# IoT_Greenhouse_V1_0_A_-_Esp32.net
KiCad netlist of a schematic drawn in Altium Designer
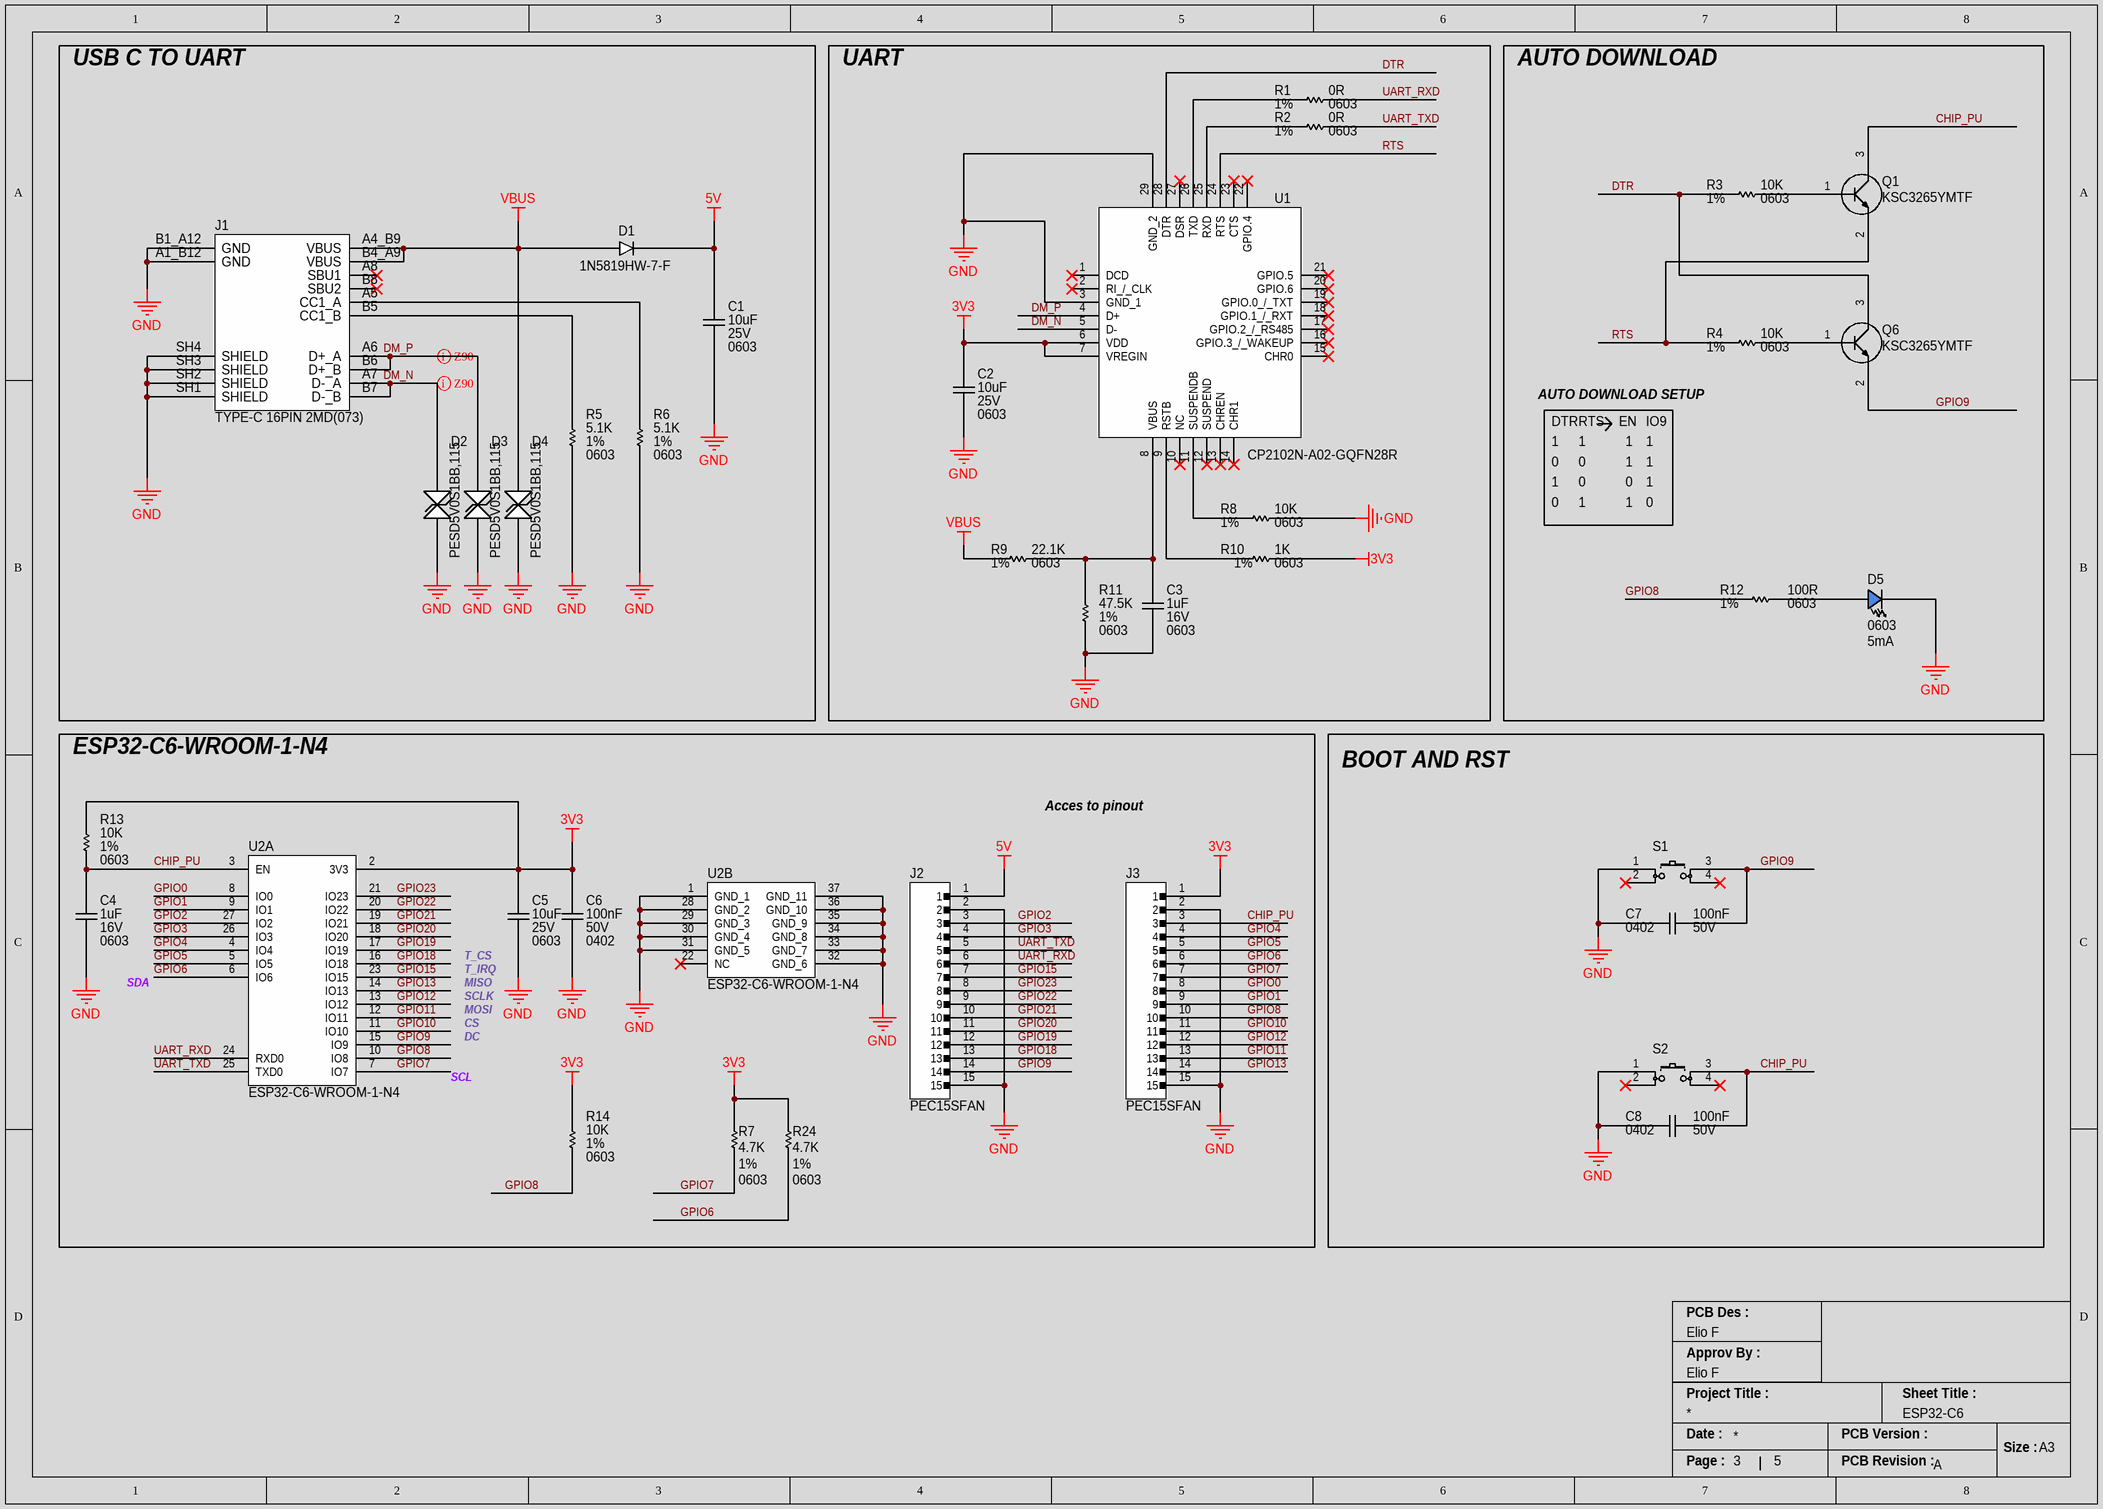
[diagram p0: IoT_Greenhouse V1.0 A - Esp32.SchDoc]

(export (version "E")
  (design (tool "Eeschema 10.0.6"))
  (components
    (comp (ref "C1")
      (value "GRM188R61E106MA73D")
      (footprint "CAP_0603_CAPC1608X08N")
      (description "Multilayer Ceramic Capacitor, 10 uF, 25 V, ± 20%, X5R, 0603 [1608 Metric]")
      (fields
        (field (name "MANUFACTURER") "Murata")
        (field (name "TOLERANCE") "20%")
        (field (name "CASE/PACKAGE") "0603")
        (field (name "CAPACITANCE") "10uF")
        (field (name "VOLTAGE RATING") "25V")
      )
      (libsource (lib "Electronic Devices_LIB") (part "CAP_10UF_25V_X5R_0603"))
    )
    (comp (ref "C2")
      (value "GRM188R61E106MA73D")
      (footprint "CAP_0603_CAPC1608X08N")
      (description "Multilayer Ceramic Capacitor, 10 uF, 25 V, ± 20%, X5R, 0603 [1608 Metric]")
      (fields
        (field (name "MANUFACTURER") "Murata")
        (field (name "TOLERANCE") "20%")
        (field (name "CASE/PACKAGE") "0603")
        (field (name "CAPACITANCE") "10uF")
        (field (name "VOLTAGE RATING") "25V")
      )
      (libsource (lib "Electronic Devices_LIB") (part "CAP_10UF_25V_X5R_0603"))
    )
    (comp (ref "C3")
      (value "CL10A105KO8NNNC")
      (footprint "CAP_0603_CAPC1608X08N")
      (description "CAP CER 1UF 16V X5R 0603")
      (fields
        (field (name "MANUFACTURER") "Samsung")
        (field (name "TOLERANCE") "10%")
        (field (name "VOLTAGE RATING") "16V")
        (field (name "CAPACITANCE") "1uF")
        (field (name "CASE/PACKAGE") "0603")
      )
      (libsource (lib "Electronic Devices_LIB") (part "CAP_1UF_16V_X5R_0603"))
    )
    (comp (ref "C4")
      (value "CL10A105KO8NNNC")
      (footprint "CAP_0603_CAPC1608X08N")
      (description "CAP CER 1UF 16V X5R 0603")
      (fields
        (field (name "MANUFACTURER") "Samsung")
        (field (name "TOLERANCE") "10%")
        (field (name "VOLTAGE RATING") "16V")
        (field (name "CAPACITANCE") "1uF")
        (field (name "CASE/PACKAGE") "0603")
      )
      (libsource (lib "Electronic Devices_LIB") (part "CAP_1UF_16V_X5R_0603"))
    )
    (comp (ref "C5")
      (value "GRM188R61E106MA73D")
      (footprint "CAP_0603_CAPC1608X08N")
      (description "Multilayer Ceramic Capacitor, 10 uF, 25 V, ± 20%, X5R, 0603 [1608 Metric]")
      (fields
        (field (name "MANUFACTURER") "Murata")
        (field (name "TOLERANCE") "20%")
        (field (name "CASE/PACKAGE") "0603")
        (field (name "CAPACITANCE") "10uF")
        (field (name "VOLTAGE RATING") "25V")
      )
      (libsource (lib "Electronic Devices_LIB") (part "CAP_10UF_25V_X5R_0603"))
    )
    (comp (ref "C6")
      (value "GRM155R71H104KE14D")
      (footprint "CAP_0402_CAPC1005X05N")
      (description "Multilayer Ceramic Capacitor, 0.1 uF, 16 V, ± 10%, X7R, 0402 [1005 Metric]")
      (fields
        (field (name "MANUFACTURER") "Murata")
        (field (name "TOLERANCE") "10%")
        (field (name "VOLTAGE RATING") "50V")
        (field (name "CAPACITANCE") "100nF")
        (field (name "CASE/PACKAGE") "0402")
      )
      (libsource (lib "Electronic Devices_LIB") (part "CAP_100NF_50V_X7R_0402"))
    )
    (comp (ref "C7")
      (value "GRM155R71H104KE14D")
      (footprint "CAP_0402_CAPC1005X05N")
      (description "Multilayer Ceramic Capacitor, 0.1 uF, 16 V, ± 10%, X7R, 0402 [1005 Metric]")
      (fields
        (field (name "MANUFACTURER") "Murata")
        (field (name "TOLERANCE") "10%")
        (field (name "VOLTAGE RATING") "50V")
        (field (name "CAPACITANCE") "100nF")
        (field (name "CASE/PACKAGE") "0402")
      )
      (libsource (lib "Electronic Devices_LIB") (part "CAP_100NF_50V_X7R_0402"))
    )
    (comp (ref "C8")
      (value "GRM155R71H104KE14D")
      (footprint "CAP_0402_CAPC1005X05N")
      (description "Multilayer Ceramic Capacitor, 0.1 uF, 16 V, ± 10%, X7R, 0402 [1005 Metric]")
      (fields
        (field (name "MANUFACTURER") "Murata")
        (field (name "TOLERANCE") "10%")
        (field (name "VOLTAGE RATING") "50V")
        (field (name "CAPACITANCE") "100nF")
        (field (name "CASE/PACKAGE") "0402")
      )
      (libsource (lib "Electronic Devices_LIB") (part "CAP_100NF_50V_X7R_0402"))
    )
    (comp (ref "D1")
      (value "1N5819HW-7-F")
      (footprint "DIO_SOD3716X145N")
      (description "Rectifier Diode, Schottky, 1 Phase, 1 Element, 1A, 40V V(RRM), Silicon")
      (fields (field (name "MANUFACTURER") "Diodes"))
      (libsource (lib "Electronic Devices_LIB") (part "DIO_RECT_40V_1A_1N5819HW-7-F"))
    )
    (comp (ref "D2")
      (value "PESD5V0S1BB,115")
      (footprint "DIO_TVS_SODFL1608X65N")
      (description "ESD Suppressor Diode TVS Bi-Dir 5V Automotive 2-Pin SOD-523 T/R / TVS DIODE 5VWM 14VC SOD523")
      (fields (field (name "MANUFACTURER") "Nexperia"))
      (libsource (lib "Electronic Devices_LIB") (part "DIO_TVS_BID_5V_PESD5V0S1BB,115"))
    )
    (comp (ref "D3")
      (value "PESD5V0S1BB,115")
      (footprint "DIO_TVS_SODFL1608X65N")
      (description "ESD Suppressor Diode TVS Bi-Dir 5V Automotive 2-Pin SOD-523 T/R / TVS DIODE 5VWM 14VC SOD523")
      (fields (field (name "MANUFACTURER") "Nexperia"))
      (libsource (lib "Electronic Devices_LIB") (part "DIO_TVS_BID_5V_PESD5V0S1BB,115"))
    )
    (comp (ref "D4")
      (value "PESD5V0S1BB,115")
      (footprint "DIO_TVS_SODFL1608X65N")
      (description "ESD Suppressor Diode TVS Bi-Dir 5V Automotive 2-Pin SOD-523 T/R / TVS DIODE 5VWM 14VC SOD523")
      (fields (field (name "MANUFACTURER") "Nexperia"))
      (libsource (lib "Electronic Devices_LIB") (part "DIO_TVS_BID_5V_PESD5V0S1BB,115"))
    )
    (comp (ref "D5")
      (value "LTST-C193TBKT-5A")
      (footprint "LED_0603-BLUE-0.75mm")
      (description "LED Uni-Color Blue 468nm 2-Pin Chip LED T/R")
      (fields
        (field (name "MANUFACTURER") "Vishay Lite-On")
        (field (name "CASE CODE (IMPERIAL)") "0603")
        (field (name "TEST CURRENT") "5mA")
      )
      (libsource (lib "Electronic Devices_LIB") (part "LED_DIO_BLUE_5mA_0603"))
    )
    (comp (ref "J1")
      (value "TYPE-C 16PIN 2MD(073)")
      (footprint "CONN_USB_C_16P")
      (description "5A 1 Surface Mount 16P Female -25℃~+85℃ Type-C SMD USB Connectors ROHS")
      (fields (field (name "MANUFACTURER") "SHOU HAN"))
      (libsource (lib "Electronic Devices_LIB") (part "CONN_USB_TYPEC_2.0_16P_TYPE-C 16PIN 2MD(073)"))
    )
    (comp (ref "J2")
      (value "PEC15SFAN")
      (footprint "HEADER_MALE_15P")
      (description "CONN HEADER .100 SINGL STR 15POS")
      (fields (field (name "MANUFACTURER") "Sullins"))
      (libsource (lib "Electronic Devices_LIB") (part "CONN_HEADER_MALE_15P_2.54mm"))
    )
    (comp (ref "J3")
      (value "PEC15SFAN")
      (footprint "HEADER_MALE_15P")
      (description "CONN HEADER .100 SINGL STR 15POS")
      (fields (field (name "MANUFACTURER") "Sullins"))
      (libsource (lib "Electronic Devices_LIB") (part "CONN_HEADER_MALE_15P_2.54mm"))
    )
    (comp (ref "Q1")
      (value "KSC3265YMTF")
      (footprint "TRANS_BJT_SOT96P237X111-3N")
      (description "KSC3265 Series 25 V CE Breakdown .8 A NPN Epitaxial Silicon Transistor - SOT-23")
      (fields (field (name "MANUFACTURER") "ON Semiconductor / Fairchild"))
      (libsource (lib "Electronic Devices_LIB") (part "TRANS_BJT_NPN_800mA_25V_KSC3265YMTF"))
    )
    (comp (ref "Q6")
      (value "KSC3265YMTF")
      (footprint "TRANS_BJT_SOT96P237X111-3N")
      (description "KSC3265 Series 25 V CE Breakdown .8 A NPN Epitaxial Silicon Transistor - SOT-23")
      (fields (field (name "MANUFACTURER") "ON Semiconductor / Fairchild"))
      (libsource (lib "Electronic Devices_LIB") (part "TRANS_BJT_NPN_800mA_25V_KSC3265YMTF"))
    )
    (comp (ref "R1")
      (value "RC0603FR-070RL")
      (footprint "RES_0603_RESC1608X04N")
      (description "RC Series 0603 0.1 W 0 Ohm Jumper Surface Mount Thick Film Chip Resistor")
      (fields
        (field (name "MANUFACTURER") "Yageo")
        (field (name "TOLERANCE") "1%")
        (field (name "RESISTANCE") "0R")
        (field (name "CASE CODE (IMPERIAL)") "0603")
      )
      (libsource (lib "Electronic Devices_LIB") (part "RES_0R_1%_100mW_0603"))
    )
    (comp (ref "R2")
      (value "RC0603FR-070RL")
      (footprint "RES_0603_RESC1608X04N")
      (description "RC Series 0603 0.1 W 0 Ohm Jumper Surface Mount Thick Film Chip Resistor")
      (fields
        (field (name "MANUFACTURER") "Yageo")
        (field (name "TOLERANCE") "1%")
        (field (name "RESISTANCE") "0R")
        (field (name "CASE CODE (IMPERIAL)") "0603")
      )
      (libsource (lib "Electronic Devices_LIB") (part "RES_0R_1%_100mW_0603"))
    )
    (comp (ref "R3")
      (value "AC0603FR-1010KL")
      (footprint "RES_0603_RESC1608X04N")
      (description "Chip Resistor Automotive Grade Thick Film 0603 10kOhm 1% Paper T/R")
      (fields
        (field (name "MANUFACTURER") "Yageo")
        (field (name "RESISTANCE") "10K")
        (field (name "TOLERANCE") "1%")
        (field (name "CASE/PACKAGE") "0603")
      )
      (libsource (lib "Electronic Devices_LIB") (part "RES_10K_1%_100mW_0603"))
    )
    (comp (ref "R4")
      (value "AC0603FR-1010KL")
      (footprint "RES_0603_RESC1608X04N")
      (description "Chip Resistor Automotive Grade Thick Film 0603 10kOhm 1% Paper T/R")
      (fields
        (field (name "MANUFACTURER") "Yageo")
        (field (name "RESISTANCE") "10K")
        (field (name "TOLERANCE") "1%")
        (field (name "CASE/PACKAGE") "0603")
      )
      (libsource (lib "Electronic Devices_LIB") (part "RES_10K_1%_100mW_0603"))
    )
    (comp (ref "R5")
      (value "RC0603FR-075K1L")
      (footprint "RES_0603_RESC1608X04N")
      (description "SMD Chip Resistor, 5.1 kOhm, ± 1%, 100 mW, 0603 [1608 Metric], Thick Film, General Purpose")
      (fields
        (field (name "MANUFACTURER") "Yageo")
        (field (name "TOLERANCE") "1%")
        (field (name "RESISTANCE") "5.1K")
        (field (name "CASE/PACKAGE") "0603")
      )
      (libsource (lib "Electronic Devices_LIB") (part "RES_5.1K_1%_100mW_0603"))
    )
    (comp (ref "R6")
      (value "RC0603FR-075K1L")
      (footprint "RES_0603_RESC1608X04N")
      (description "SMD Chip Resistor, 5.1 kOhm, ± 1%, 100 mW, 0603 [1608 Metric], Thick Film, General Purpose")
      (fields
        (field (name "MANUFACTURER") "Yageo")
        (field (name "TOLERANCE") "1%")
        (field (name "RESISTANCE") "5.1K")
        (field (name "CASE/PACKAGE") "0603")
      )
      (libsource (lib "Electronic Devices_LIB") (part "RES_5.1K_1%_100mW_0603"))
    )
    (comp (ref "R7")
      (value "RC0603FR-074K7L")
      (footprint "RES_0603_RESC1608X04N")
      (description "Res Thick Film 0603 4.7K Ohm 1% 1/10W ±100ppm/°C Molded SMD Paper T/R")
      (fields
        (field (name "MANUFACTURER") "Yageo")
        (field (name "RESISTANCE") "4.7K")
        (field (name "TOLERANCE") "1%")
        (field (name "CASE/PACKAGE") "0603")
      )
      (libsource (lib "Electronic Devices_LIB") (part "RES_4.7K_1%_100mW_0603"))
    )
    (comp (ref "R8")
      (value "AC0603FR-1010KL")
      (footprint "RES_0603_RESC1608X04N")
      (description "Chip Resistor Automotive Grade Thick Film 0603 10kOhm 1% Paper T/R")
      (fields
        (field (name "MANUFACTURER") "Yageo")
        (field (name "RESISTANCE") "10K")
        (field (name "TOLERANCE") "1%")
        (field (name "CASE/PACKAGE") "0603")
      )
      (libsource (lib "Electronic Devices_LIB") (part "RES_10K_1%_100mW_0603"))
    )
    (comp (ref "R9")
      (value "RC0603FR-0722K1L")
      (footprint "RES_0603_RESC1608X04N")
      (description "SMD Chip Resistor, 22.1 kOhm, ± 1%, 100 mW, 0603 [1608 Metric], Thick Film, General Purpose")
      (fields
        (field (name "MANUFACTURER") "Yageo")
        (field (name "RESISTANCE") "22.1K")
        (field (name "TOLERANCE") "1%")
        (field (name "CASE/PACKAGE") "0603")
      )
      (libsource (lib "Electronic Devices_LIB") (part "RES_22.1K_1%_100mW_0603"))
    )
    (comp (ref "R10")
      (value "AC0603FR-101KL")
      (footprint "RES_0603_RESC1608X04N")
      (description "Chip Resistor Automotive Grade Thick Film 0603 1kOhm 1% Paper T/R")
      (fields
        (field (name "MANUFACTURER") "Yageo")
        (field (name "RESISTANCE") "1K")
        (field (name "TOLERANCE") "1%")
        (field (name "CASE/PACKAGE") "0603")
      )
      (libsource (lib "Electronic Devices_LIB") (part "RES_1K_1%_100mW_0603"))
    )
    (comp (ref "R11")
      (value "AC0603FR-0747K5L")
      (footprint "RES_0603_RESC1608X04N")
      (description "SMD Chip Resistor, 47.5 kOhm, ± 1%, 100 mW, 0603 [1608 Metric], Thick Film, General Purpose")
      (fields
        (field (name "MANUFACTURER") "Yageo")
        (field (name "TOLERANCE") "1%")
        (field (name "RESISTANCE") "47.5K")
        (field (name "CASE/PACKAGE") "0603")
      )
      (libsource (lib "Electronic Devices_LIB") (part "RES_47.5K_1%_100mW_0603"))
    )
    (comp (ref "R12")
      (value "ERJ3EKF1000V")
      (footprint "CAP_0603_CAPC1608X08N")
      (description "Res Thick Film 0603 100 Ohm 1% 1/10W ±100ppm/°C Molded SMD Punched Carrier T/R")
      (fields
        (field (name "MANUFACTURER") "Panasonic")
        (field (name "CASE CODE (IMPERIAL)") "0603")
        (field (name "TOLERANCE") "1%")
        (field (name "RESISTANCE") "100R")
      )
      (libsource (lib "Electronic Devices_LIB") (part "RES_100R_1%_100MW_0603"))
    )
    (comp (ref "R13")
      (value "AC0603FR-1010KL")
      (footprint "RES_0603_RESC1608X04N")
      (description "Chip Resistor Automotive Grade Thick Film 0603 10kOhm 1% Paper T/R")
      (fields
        (field (name "MANUFACTURER") "Yageo")
        (field (name "RESISTANCE") "10K")
        (field (name "TOLERANCE") "1%")
        (field (name "CASE/PACKAGE") "0603")
      )
      (libsource (lib "Electronic Devices_LIB") (part "RES_10K_1%_100mW_0603"))
    )
    (comp (ref "R14")
      (value "AC0603FR-1010KL")
      (footprint "RES_0603_RESC1608X04N")
      (description "Chip Resistor Automotive Grade Thick Film 0603 10kOhm 1% Paper T/R")
      (fields
        (field (name "MANUFACTURER") "Yageo")
        (field (name "RESISTANCE") "10K")
        (field (name "TOLERANCE") "1%")
        (field (name "CASE/PACKAGE") "0603")
      )
      (libsource (lib "Electronic Devices_LIB") (part "RES_10K_1%_100mW_0603"))
    )
    (comp (ref "R24")
      (value "RC0603FR-074K7L")
      (footprint "RES_0603_RESC1608X04N")
      (description "Res Thick Film 0603 4.7K Ohm 1% 1/10W ±100ppm/°C Molded SMD Paper T/R")
      (fields
        (field (name "MANUFACTURER") "Yageo")
        (field (name "RESISTANCE") "4.7K")
        (field (name "TOLERANCE") "1%")
        (field (name "CASE/PACKAGE") "0603")
      )
      (libsource (lib "Electronic Devices_LIB") (part "RES_4.7K_1%_100mW_0603"))
    )
    (comp (ref "S1")
      (value "PTS526SK15SMTR2LFS")
      (footprint "SWT_NO_PTS526SK15SMTR2LFS")
      (description "Switch Tactile N.O. SPST Round Button Gull Wing 0.05A 12VDC 200000Cycles 2.55N SMD T/R")
      (fields (field (name "MANUFACTURER") "ITT C&K"))
      (libsource (lib "Electronic Devices_LIB") (part "SWITCH_NO_SPST_0.05A"))
    )
    (comp (ref "S2")
      (value "PTS526SK15SMTR2LFS")
      (footprint "SWT_NO_PTS526SK15SMTR2LFS")
      (description "Switch Tactile N.O. SPST Round Button Gull Wing 0.05A 12VDC 200000Cycles 2.55N SMD T/R")
      (fields (field (name "MANUFACTURER") "ITT C&K"))
      (libsource (lib "Electronic Devices_LIB") (part "SWITCH_NO_SPST_0.05A"))
    )
    (comp (ref "U1")
      (value "CP2102N-A02-GQFN28R")
      (footprint "IC_BRIDGE_UART_QFN50P500X500X80-29N-D")
      (description "Full Speed USB to UART Bridge USB 2.0 3.3V T/R Automotive 28-Pin QFN EP")
      (fields (field (name "MANUFACTURER") "Silicon Labs"))
      (libsource (lib "Electronic Devices_LIB") (part "IC_BRIDGE_UART_CP2102N-A02-GQFN28R"))
    )
    (comp (ref "U2")
      (value "ESP32-C6-WROOM-1-N4")
      (footprint "IC_MODULE_ESP32C6WROOM1N4")
      (description "ESP32-C6-WROOM-1-N4 Engineering Module - 4 MB Quad SPI Flash")
      (fields (field (name "MANUFACTURER") "Espressif Systems"))
      (libsource (lib "Electronic Devices_LIB") (part "IC_MODULE_ESP32-C6-WROOM-1-N4"))
    )
  )
  (nets
    (net (code "1") (name "/CHIP_PU") (class "Default")
      (node (ref "C4") (pin "2") (pinfunction "2_2") (pintype "passive"))
      (node (ref "C8") (pin "1") (pinfunction "1_1") (pintype "passive"))
      (node (ref "J3") (pin "3") (pinfunction "3_3") (pintype "passive"))
      (node (ref "Q1") (pin "3") (pinfunction "C_3") (pintype "passive"))
      (node (ref "R13") (pin "2") (pinfunction "2_2") (pintype "passive"))
      (node (ref "S2") (pin "3") (pinfunction "NO1_3") (pintype "passive"))
      (node (ref "U2") (pin "3") (pinfunction "EN_3") (pintype "passive"))
    )
    (net (code "2") (name "/DM_N") (class "Default")
      (node (ref "D2") (pin "2") (pinfunction "K2_2") (pintype "passive"))
      (node (ref "J1") (pin "A7") (pinfunction "D-_A_A7") (pintype "passive"))
      (node (ref "J1") (pin "B7") (pinfunction "D-_B_B7") (pintype "passive"))
      (node (ref "U1") (pin "5") (pinfunction "D-_5") (pintype "passive"))
    )
    (net (code "3") (name "/DM_P") (class "Default")
      (node (ref "D3") (pin "2") (pinfunction "K2_2") (pintype "passive"))
      (node (ref "J1") (pin "A6") (pinfunction "D+_A_A6") (pintype "passive"))
      (node (ref "J1") (pin "B6") (pinfunction "D+_B_B6") (pintype "passive"))
      (node (ref "U1") (pin "4") (pinfunction "D+_4") (pintype "passive"))
    )
    (net (code "4") (name "/DTR") (class "Default")
      (node (ref "Q6") (pin "3") (pinfunction "C_3") (pintype "passive"))
      (node (ref "R3") (pin "2") (pinfunction "2_2") (pintype "passive"))
      (node (ref "U1") (pin "28") (pinfunction "DTR_28") (pintype "passive"))
    )
    (net (code "5") (name "/GPIO0") (class "Default")
      (node (ref "J3") (pin "8") (pinfunction "8_8") (pintype "passive"))
      (node (ref "U2") (pin "8") (pinfunction "IO0_8") (pintype "passive"))
    )
    (net (code "6") (name "/GPIO1") (class "Default")
      (node (ref "J3") (pin "9") (pinfunction "9_9") (pintype "passive"))
      (node (ref "U2") (pin "9") (pinfunction "IO1_9") (pintype "passive"))
    )
    (net (code "7") (name "/GPIO2") (class "Default")
      (node (ref "J2") (pin "3") (pinfunction "3_3") (pintype "passive"))
      (node (ref "U2") (pin "27") (pinfunction "IO2_27") (pintype "passive"))
    )
    (net (code "8") (name "/GPIO3") (class "Default")
      (node (ref "J2") (pin "4") (pinfunction "4_4") (pintype "passive"))
      (node (ref "U2") (pin "26") (pinfunction "IO3_26") (pintype "passive"))
    )
    (net (code "9") (name "/GPIO4") (class "Default")
      (node (ref "J3") (pin "4") (pinfunction "4_4") (pintype "passive"))
      (node (ref "U2") (pin "4") (pinfunction "IO4_4") (pintype "passive"))
    )
    (net (code "10") (name "/GPIO5") (class "Default")
      (node (ref "J3") (pin "5") (pinfunction "5_5") (pintype "passive"))
      (node (ref "U2") (pin "5") (pinfunction "IO5_5") (pintype "passive"))
    )
    (net (code "11") (name "/GPIO6") (class "Default")
      (node (ref "J3") (pin "6") (pinfunction "6_6") (pintype "passive"))
      (node (ref "R24") (pin "1") (pinfunction "1_1") (pintype "passive"))
      (node (ref "U2") (pin "6") (pinfunction "IO6_6") (pintype "passive"))
    )
    (net (code "12") (name "/GPIO7") (class "Default")
      (node (ref "J3") (pin "7") (pinfunction "7_7") (pintype "passive"))
      (node (ref "R7") (pin "1") (pinfunction "1_1") (pintype "passive"))
      (node (ref "U2") (pin "7") (pinfunction "IO7_7") (pintype "passive"))
    )
    (net (code "13") (name "/GPIO8") (class "Default")
      (node (ref "J3") (pin "10") (pinfunction "10_10") (pintype "passive"))
      (node (ref "R12") (pin "1") (pinfunction "1_1") (pintype "passive"))
      (node (ref "R14") (pin "2") (pinfunction "2_2") (pintype "passive"))
      (node (ref "U2") (pin "10") (pinfunction "IO8_10") (pintype "passive"))
    )
    (net (code "14") (name "/GPIO9") (class "Default")
      (node (ref "C7") (pin "1") (pinfunction "1_1") (pintype "passive"))
      (node (ref "J2") (pin "14") (pinfunction "14_14") (pintype "passive"))
      (node (ref "Q6") (pin "2") (pinfunction "E_2") (pintype "passive"))
      (node (ref "S1") (pin "3") (pinfunction "NO1_3") (pintype "passive"))
      (node (ref "U2") (pin "15") (pinfunction "IO9_15") (pintype "passive"))
    )
    (net (code "15") (name "/GPIO10") (class "Default")
      (node (ref "J3") (pin "11") (pinfunction "11_11") (pintype "passive"))
      (node (ref "U2") (pin "11") (pinfunction "IO10_11") (pintype "passive"))
    )
    (net (code "16") (name "/GPIO11") (class "Default")
      (node (ref "J3") (pin "13") (pinfunction "13_13") (pintype "passive"))
      (node (ref "U2") (pin "12") (pinfunction "IO11_12") (pintype "passive"))
    )
    (net (code "17") (name "/GPIO12") (class "Default")
      (node (ref "J3") (pin "12") (pinfunction "12_12") (pintype "passive"))
      (node (ref "U2") (pin "13") (pinfunction "IO12_13") (pintype "passive"))
    )
    (net (code "18") (name "/GPIO13") (class "Default")
      (node (ref "J3") (pin "14") (pinfunction "14_14") (pintype "passive"))
      (node (ref "U2") (pin "14") (pinfunction "IO13_14") (pintype "passive"))
    )
    (net (code "19") (name "/GPIO15") (class "Default")
      (node (ref "J2") (pin "7") (pinfunction "7_7") (pintype "passive"))
      (node (ref "U2") (pin "23") (pinfunction "IO15_23") (pintype "passive"))
    )
    (net (code "20") (name "/GPIO18") (class "Default")
      (node (ref "J2") (pin "13") (pinfunction "13_13") (pintype "passive"))
      (node (ref "U2") (pin "16") (pinfunction "IO18_16") (pintype "passive"))
    )
    (net (code "21") (name "/GPIO19") (class "Default")
      (node (ref "J2") (pin "12") (pinfunction "12_12") (pintype "passive"))
      (node (ref "U2") (pin "17") (pinfunction "IO19_17") (pintype "passive"))
    )
    (net (code "22") (name "/GPIO20") (class "Default")
      (node (ref "J2") (pin "11") (pinfunction "11_11") (pintype "passive"))
      (node (ref "U2") (pin "18") (pinfunction "IO20_18") (pintype "passive"))
    )
    (net (code "23") (name "/GPIO21") (class "Default")
      (node (ref "J2") (pin "10") (pinfunction "10_10") (pintype "passive"))
      (node (ref "U2") (pin "19") (pinfunction "IO21_19") (pintype "passive"))
    )
    (net (code "24") (name "/GPIO22") (class "Default")
      (node (ref "J2") (pin "9") (pinfunction "9_9") (pintype "passive"))
      (node (ref "U2") (pin "20") (pinfunction "IO22_20") (pintype "passive"))
    )
    (net (code "25") (name "/GPIO23") (class "Default")
      (node (ref "J2") (pin "8") (pinfunction "8_8") (pintype "passive"))
      (node (ref "U2") (pin "21") (pinfunction "IO23_21") (pintype "passive"))
    )
    (net (code "26") (name "/RTS") (class "Default")
      (node (ref "Q1") (pin "2") (pinfunction "E_2") (pintype "passive"))
      (node (ref "R4") (pin "2") (pinfunction "2_2") (pintype "passive"))
      (node (ref "U1") (pin "24") (pinfunction "RTS_24") (pintype "passive"))
    )
    (net (code "27") (name "/UART_RXD") (class "Default")
      (node (ref "J2") (pin "6") (pinfunction "6_6") (pintype "passive"))
      (node (ref "R1") (pin "1") (pinfunction "1_1") (pintype "passive"))
      (node (ref "U2") (pin "24") (pinfunction "RXD0_24") (pintype "passive"))
    )
    (net (code "28") (name "/UART_TXD") (class "Default")
      (node (ref "J2") (pin "5") (pinfunction "5_5") (pintype "passive"))
      (node (ref "R2") (pin "1") (pinfunction "1_1") (pintype "passive"))
      (node (ref "U2") (pin "25") (pinfunction "TXD0_25") (pintype "passive"))
    )
    (net (code "29") (name "3V3") (class "Default")
      (node (ref "C2") (pin "2") (pinfunction "2_2") (pintype "passive"))
      (node (ref "C5") (pin "2") (pinfunction "2_2") (pintype "passive"))
      (node (ref "C6") (pin "2") (pinfunction "2_2") (pintype "passive"))
      (node (ref "J3") (pin "1") (pinfunction "1_1") (pintype "passive"))
      (node (ref "R10") (pin "2") (pinfunction "2_2") (pintype "passive"))
      (node (ref "R13") (pin "1") (pinfunction "1_1") (pintype "passive"))
      (node (ref "R14") (pin "1") (pinfunction "1_1") (pintype "passive"))
      (node (ref "R24") (pin "2") (pinfunction "2_2") (pintype "passive"))
      (node (ref "R7") (pin "2") (pinfunction "2_2") (pintype "passive"))
      (node (ref "U1") (pin "6") (pinfunction "VDD_6") (pintype "passive"))
      (node (ref "U1") (pin "7") (pinfunction "VREGIN_7") (pintype "passive"))
      (node (ref "U2") (pin "2") (pinfunction "3V3_2") (pintype "passive"))
    )
    (net (code "30") (name "5V") (class "Default")
      (node (ref "C1") (pin "2") (pinfunction "2_2") (pintype "passive"))
      (node (ref "D1") (pin "1") (pinfunction "K_1") (pintype "passive"))
      (node (ref "J2") (pin "1") (pinfunction "1_1") (pintype "passive"))
    )
    (net (code "31") (name "GND") (class "Default")
      (node (ref "C1") (pin "1") (pinfunction "1_1") (pintype "passive"))
      (node (ref "C2") (pin "1") (pinfunction "1_1") (pintype "passive"))
      (node (ref "C3") (pin "1") (pinfunction "1_1") (pintype "passive"))
      (node (ref "C4") (pin "1") (pinfunction "1_1") (pintype "passive"))
      (node (ref "C5") (pin "1") (pinfunction "1_1") (pintype "passive"))
      (node (ref "C6") (pin "1") (pinfunction "1_1") (pintype "passive"))
      (node (ref "C7") (pin "2") (pinfunction "2_2") (pintype "passive"))
      (node (ref "C8") (pin "2") (pinfunction "2_2") (pintype "passive"))
      (node (ref "D2") (pin "1") (pinfunction "K1_1") (pintype "passive"))
      (node (ref "D3") (pin "1") (pinfunction "K1_1") (pintype "passive"))
      (node (ref "D4") (pin "1") (pinfunction "K1_1") (pintype "passive"))
      (node (ref "D5") (pin "1") (pinfunction "C_1") (pintype "passive"))
      (node (ref "J1") (pin "A1_B12") (pinfunction "GND_A1_B12") (pintype "power_in"))
      (node (ref "J1") (pin "B1_A12") (pinfunction "GND_B1_A12") (pintype "power_in"))
      (node (ref "J1") (pin "SH1") (pinfunction "SHIELD_SH1") (pintype "passive"))
      (node (ref "J1") (pin "SH2") (pinfunction "SHIELD_SH2") (pintype "passive"))
      (node (ref "J1") (pin "SH3") (pinfunction "SHIELD_SH3") (pintype "passive"))
      (node (ref "J1") (pin "SH4") (pinfunction "SHIELD_SH4") (pintype "passive"))
      (node (ref "J2") (pin "15") (pinfunction "15_15") (pintype "passive"))
      (node (ref "J2") (pin "2") (pinfunction "2_2") (pintype "passive"))
      (node (ref "J3") (pin "15") (pinfunction "15_15") (pintype "passive"))
      (node (ref "J3") (pin "2") (pinfunction "2_2") (pintype "passive"))
      (node (ref "R11") (pin "1") (pinfunction "1_1") (pintype "passive"))
      (node (ref "R5") (pin "1") (pinfunction "1_1") (pintype "passive"))
      (node (ref "R6") (pin "1") (pinfunction "1_1") (pintype "passive"))
      (node (ref "R8") (pin "2") (pinfunction "2_2") (pintype "passive"))
      (node (ref "S1") (pin "1") (pinfunction "COM_1_1") (pintype "passive"))
      (node (ref "S2") (pin "1") (pinfunction "COM_1_1") (pintype "passive"))
      (node (ref "U1") (pin "29") (pinfunction "GND_2_29") (pintype "passive"))
      (node (ref "U1") (pin "3") (pinfunction "GND_1_3") (pintype "passive"))
      (node (ref "U2") (pin "1") (pinfunction "GND_1_1") (pintype "passive"))
      (node (ref "U2") (pin "28") (pinfunction "GND_2_28") (pintype "passive"))
      (node (ref "U2") (pin "29") (pinfunction "GND_3_29") (pintype "passive"))
      (node (ref "U2") (pin "30") (pinfunction "GND_4_30") (pintype "passive"))
      (node (ref "U2") (pin "31") (pinfunction "GND_5_31") (pintype "passive"))
      (node (ref "U2") (pin "32") (pinfunction "GND_6_32") (pintype "passive"))
      (node (ref "U2") (pin "33") (pinfunction "GND_7_33") (pintype "passive"))
      (node (ref "U2") (pin "34") (pinfunction "GND_8_34") (pintype "passive"))
      (node (ref "U2") (pin "35") (pinfunction "GND_9_35") (pintype "passive"))
      (node (ref "U2") (pin "36") (pinfunction "GND_10_36") (pintype "passive"))
      (node (ref "U2") (pin "37") (pinfunction "GND_11_37") (pintype "passive"))
    )
    (net (code "32") (name "Net-(D5-A)") (class "Default")
      (node (ref "D5") (pin "2") (pinfunction "A_2") (pintype "passive"))
      (node (ref "R12") (pin "2") (pinfunction "2_2") (pintype "passive"))
    )
    (net (code "33") (name "Net-(J1-CC1_A)") (class "Default")
      (node (ref "J1") (pin "A5") (pinfunction "CC1_A_A5") (pintype "passive"))
      (node (ref "R6") (pin "2") (pinfunction "2_2") (pintype "passive"))
    )
    (net (code "34") (name "Net-(J1-CC1_B)") (class "Default")
      (node (ref "J1") (pin "B5") (pinfunction "CC1_B_B5") (pintype "passive"))
      (node (ref "R5") (pin "2") (pinfunction "2_2") (pintype "passive"))
    )
    (net (code "35") (name "Net-(Q1-B)") (class "Default")
      (node (ref "Q1") (pin "1") (pinfunction "B_1") (pintype "passive"))
      (node (ref "R3") (pin "1") (pinfunction "1_1") (pintype "passive"))
    )
    (net (code "36") (name "Net-(Q6-B)") (class "Default")
      (node (ref "Q6") (pin "1") (pinfunction "B_1") (pintype "passive"))
      (node (ref "R4") (pin "1") (pinfunction "1_1") (pintype "passive"))
    )
    (net (code "37") (name "Net-(U1-RSTB)") (class "Default")
      (node (ref "R10") (pin "1") (pinfunction "1_1") (pintype "passive"))
      (node (ref "U1") (pin "9") (pinfunction "RSTB_9") (pintype "passive"))
    )
    (net (code "38") (name "Net-(U1-RXD)") (class "Default")
      (node (ref "R2") (pin "2") (pinfunction "2_2") (pintype "passive"))
      (node (ref "U1") (pin "25") (pinfunction "RXD_25") (pintype "passive"))
    )
    (net (code "39") (name "Net-(U1-SUSPENDB)") (class "Default")
      (node (ref "R8") (pin "1") (pinfunction "1_1") (pintype "passive"))
      (node (ref "U1") (pin "11") (pinfunction "SUSPENDB_11") (pintype "passive"))
    )
    (net (code "40") (name "Net-(U1-TXD)") (class "Default")
      (node (ref "R1") (pin "2") (pinfunction "2_2") (pintype "passive"))
      (node (ref "U1") (pin "26") (pinfunction "TXD_26") (pintype "passive"))
    )
    (net (code "41") (name "Net-(U1-VBUS)") (class "Default")
      (node (ref "C3") (pin "2") (pinfunction "2_2") (pintype "passive"))
      (node (ref "R11") (pin "2") (pinfunction "2_2") (pintype "passive"))
      (node (ref "R9") (pin "2") (pinfunction "2_2") (pintype "passive"))
      (node (ref "U1") (pin "8") (pinfunction "VBUS_8") (pintype "passive"))
    )
    (net (code "42") (name "VBUS") (class "Default")
      (node (ref "D1") (pin "2") (pinfunction "A_2") (pintype "passive"))
      (node (ref "D4") (pin "2") (pinfunction "K2_2") (pintype "passive"))
      (node (ref "J1") (pin "A4_B9") (pinfunction "VBUS_A4_B9") (pintype "power_in"))
      (node (ref "J1") (pin "B4_A9") (pinfunction "VBUS_B4_A9") (pintype "power_in"))
      (node (ref "R9") (pin "1") (pinfunction "1_1") (pintype "passive"))
    )
    (net (code "43") (name "unconnected-(J1-SBU1-PadA8)") (class "Default")
      (node (ref "J1") (pin "A8") (pinfunction "SBU1_A8") (pintype "passive+no_connect"))
    )
    (net (code "44") (name "unconnected-(J1-SBU2-PadB8)") (class "Default")
      (node (ref "J1") (pin "B8") (pinfunction "SBU2_B8") (pintype "passive+no_connect"))
    )
    (net (code "45") (name "unconnected-(S1-COM2-Pad2)") (class "Default")
      (node (ref "S1") (pin "2") (pinfunction "COM2_2") (pintype "passive+no_connect"))
    )
    (net (code "46") (name "unconnected-(S1-NO2-Pad4)") (class "Default")
      (node (ref "S1") (pin "4") (pinfunction "NO2_4") (pintype "passive+no_connect"))
    )
    (net (code "47") (name "unconnected-(S2-COM2-Pad2)") (class "Default")
      (node (ref "S2") (pin "2") (pinfunction "COM2_2") (pintype "passive+no_connect"))
    )
    (net (code "48") (name "unconnected-(S2-NO2-Pad4)") (class "Default")
      (node (ref "S2") (pin "4") (pinfunction "NO2_4") (pintype "passive+no_connect"))
    )
    (net (code "49") (name "unconnected-(U1-CHR0-Pad15)") (class "Default")
      (node (ref "U1") (pin "15") (pinfunction "CHR0_15") (pintype "passive+no_connect"))
    )
    (net (code "50") (name "unconnected-(U1-CHR1-Pad14)") (class "Default")
      (node (ref "U1") (pin "14") (pinfunction "CHR1_14") (pintype "passive+no_connect"))
    )
    (net (code "51") (name "unconnected-(U1-CHREN-Pad13)") (class "Default")
      (node (ref "U1") (pin "13") (pinfunction "CHREN_13") (pintype "passive+no_connect"))
    )
    (net (code "52") (name "unconnected-(U1-CTS-Pad23)") (class "Default")
      (node (ref "U1") (pin "23") (pinfunction "CTS_23") (pintype "passive+no_connect"))
    )
    (net (code "53") (name "unconnected-(U1-DCD-Pad1)") (class "Default")
      (node (ref "U1") (pin "1") (pinfunction "DCD_1") (pintype "passive+no_connect"))
    )
    (net (code "54") (name "unconnected-(U1-DSR-Pad27)") (class "Default")
      (node (ref "U1") (pin "27") (pinfunction "DSR_27") (pintype "passive+no_connect"))
    )
    (net (code "55") (name "unconnected-(U1-GPIO.0_{slash}_TXT-Pad19)") (class "Default")
      (node (ref "U1") (pin "19") (pinfunction "GPIO.0_/_TXT_19") (pintype "passive+no_connect"))
    )
    (net (code "56") (name "unconnected-(U1-GPIO.1_{slash}_RXT-Pad18)") (class "Default")
      (node (ref "U1") (pin "18") (pinfunction "GPIO.1_/_RXT_18") (pintype "passive+no_connect"))
    )
    (net (code "57") (name "unconnected-(U1-GPIO.2_{slash}_RS485-Pad17)") (class "Default")
      (node (ref "U1") (pin "17") (pinfunction "GPIO.2_/_RS485_17") (pintype "passive+no_connect"))
    )
    (net (code "58") (name "unconnected-(U1-GPIO.3_{slash}_WAKEUP-Pad16)") (class "Default")
      (node (ref "U1") (pin "16") (pinfunction "GPIO.3_/_WAKEUP_16") (pintype "passive+no_connect"))
    )
    (net (code "59") (name "unconnected-(U1-GPIO.4-Pad22)") (class "Default")
      (node (ref "U1") (pin "22") (pinfunction "GPIO.4_22") (pintype "passive+no_connect"))
    )
    (net (code "60") (name "unconnected-(U1-GPIO.5-Pad21)") (class "Default")
      (node (ref "U1") (pin "21") (pinfunction "GPIO.5_21") (pintype "passive+no_connect"))
    )
    (net (code "61") (name "unconnected-(U1-GPIO.6-Pad20)") (class "Default")
      (node (ref "U1") (pin "20") (pinfunction "GPIO.6_20") (pintype "passive+no_connect"))
    )
    (net (code "62") (name "unconnected-(U1-NC-Pad10)") (class "Default")
      (node (ref "U1") (pin "10") (pinfunction "NC_10") (pintype "passive+no_connect"))
    )
    (net (code "63") (name "unconnected-(U1-RI_{slash}_CLK-Pad2)") (class "Default")
      (node (ref "U1") (pin "2") (pinfunction "RI_/_CLK_2") (pintype "passive+no_connect"))
    )
    (net (code "64") (name "unconnected-(U1-SUSPEND-Pad12)") (class "Default")
      (node (ref "U1") (pin "12") (pinfunction "SUSPEND_12") (pintype "passive+no_connect"))
    )
    (net (code "65") (name "unconnected-(U2B-NC-Pad22)") (class "Default")
      (node (ref "U2") (pin "22") (pinfunction "NC_22") (pintype "passive+no_connect"))
    )
  )
)
